# OpenRing_Memory.net
KiCad netlist of a schematic drawn in Altium Designer
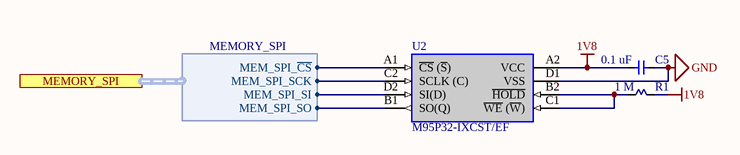
[diagram p0: OpenRing_Memory.SchDoc]

(export (version "E")
  (design (tool "Eeschema 10.0.6"))
  (components
    (comp (ref "C5")
      (value "0.1 uF")
      (footprint "CAPC1005X05N")
      (description "CAP CER 0.1UF 16V X5R 0402")
      (fields
        (field (name "MANUFACTURER") "Murata Electronics")
        (field (name "MANUFACTURER PART NUMBER") "GRM155R61C104KA88D")
      )
      (libsource (lib "OpenRingComponents") (part "GRM155R61C104KA88D"))
    )
    (comp (ref "R1")
      (value "1 M")
      (footprint "RESC1005X04N")
      (description "RES SMD 1M OHM 1% 1/10W 0402")
      (fields
        (field (name "MANUFACTURER") "Panasonic Electronic Components")
        (field (name "MANUFACTURER PART NUMBER") "ERJ-2RKF1004X")
      )
      (libsource (lib "OpenRingComponents") (part "ERJ-2RKF1004X"))
    )
    (comp (ref "U2")
      (value "M95P32-IXCST/EF")
      (footprint "BGA8C70P2X4_153X261X58")
      (description "M95P32-I Series 32 Mb (4 M x 8) 80 MHz SPI EEPROM Memory IC - WLCSP-8")
      (fields (field (name "MANUFACTURER") "STMicroelectronics"))
      (libsource (lib "OpenRingComponents") (part "M95P32-IXCST/EF"))
    )
  )
  (nets
    (net (code "2") (name "/MEM_SPI_SCK") (class "Default")
      (node (ref "U2") (pin "C2") (pinfunction "SCLK_(C)_C2") (pintype "input"))
    )
    (net (code "3") (name "/MEM_SPI_SI") (class "Default")
      (node (ref "U2") (pin "D2") (pinfunction "SI(D)_D2") (pintype "input"))
    )
    (net (code "4") (name "/MEM_SPI_SO") (class "Default")
      (node (ref "U2") (pin "B1") (pinfunction "SO(Q)_B1") (pintype "output"))
    )
    (net (code "5") (name "/MEM_SPI_~{CS}") (class "Default")
      (node (ref "U2") (pin "A1") (pinfunction "~{CS}_(~{S})_A1") (pintype "input"))
    )
    (net (code "7") (name "1V8") (class "Default")
      (node (ref "C5") (pin "2") (pinfunction "2_2") (pintype "passive"))
      (node (ref "R1") (pin "2") (pinfunction "2_2") (pintype "passive"))
      (node (ref "U2") (pin "A2") (pinfunction "VCC_A2") (pintype "power_in"))
    )
    (net (code "8") (name "GND") (class "Default")
      (node (ref "C5") (pin "1") (pinfunction "1_1") (pintype "passive"))
      (node (ref "U2") (pin "D1") (pinfunction "VSS_D1") (pintype "power_in"))
    )
    (net (code "9") (name "Net-(U2-~{HOLD})") (class "Default")
      (node (ref "R1") (pin "1") (pinfunction "1_1") (pintype "passive"))
      (node (ref "U2") (pin "B2") (pinfunction "~{HOLD}_B2") (pintype "input"))
      (node (ref "U2") (pin "C1") (pinfunction "~{WE}_(~{W})_C1") (pintype "input"))
    )
  )
)
